# drives.net
KiCad netlist of a schematic drawn in EAGLE
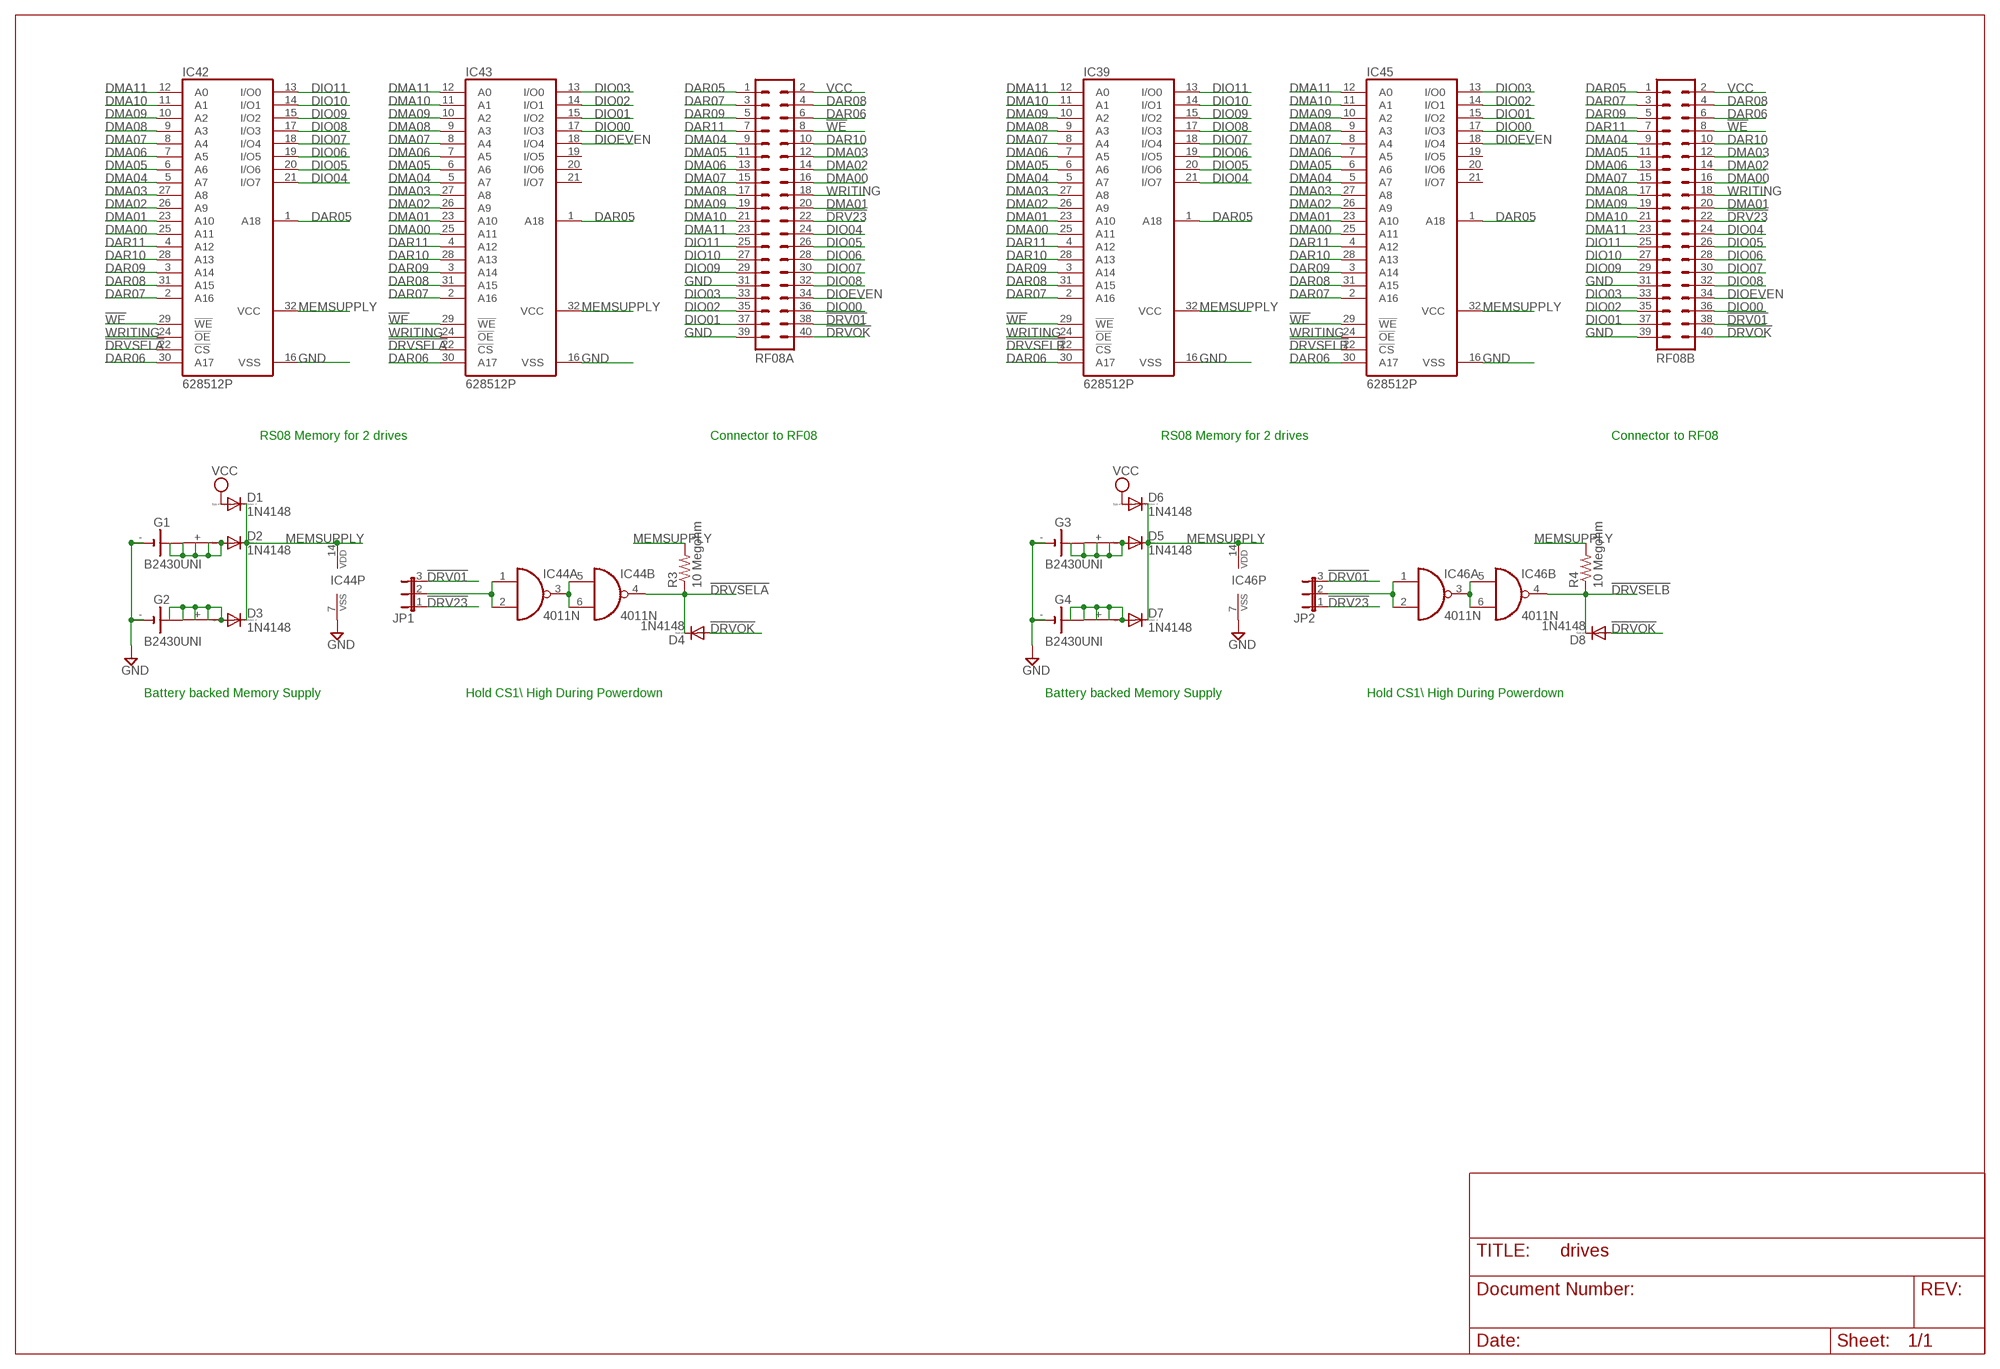
[diagram p0: schematic, sheet 1]

(export (version "E")
  (design (tool "Eeschema 10.0.6"))
  (components
    (comp (ref "D1")
      (value "1N4148")
      (footprint "eagle-import:DO35-10")
      (libsource (lib "eagle-import") (part "1N4148DO35-10"))
    )
    (comp (ref "D2")
      (value "1N4148")
      (footprint "eagle-import:DO35-10")
      (libsource (lib "eagle-import") (part "1N4148DO35-10"))
    )
    (comp (ref "D3")
      (value "1N4148")
      (footprint "eagle-import:DO35-10")
      (libsource (lib "eagle-import") (part "1N4148DO35-10"))
    )
    (comp (ref "D4")
      (value "1N4148")
      (footprint "eagle-import:DO35-10")
      (libsource (lib "eagle-import") (part "1N4148DO35-10"))
    )
    (comp (ref "D5")
      (value "1N4148")
      (footprint "eagle-import:DO35-10")
      (libsource (lib "eagle-import") (part "1N4148DO35-10"))
    )
    (comp (ref "D6")
      (value "1N4148")
      (footprint "eagle-import:DO35-10")
      (libsource (lib "eagle-import") (part "1N4148DO35-10"))
    )
    (comp (ref "D7")
      (value "1N4148")
      (footprint "eagle-import:DO35-10")
      (libsource (lib "eagle-import") (part "1N4148DO35-10"))
    )
    (comp (ref "D8")
      (value "1N4148")
      (footprint "eagle-import:DO35-10")
      (libsource (lib "eagle-import") (part "1N4148DO35-10"))
    )
    (comp (ref "G1")
      (value "B2430UNI")
      (footprint "eagle-import:B2430UNI")
      (libsource (lib "eagle-import") (part "B2430UNI"))
    )
    (comp (ref "G2")
      (value "B2430UNI")
      (footprint "eagle-import:B2430UNI")
      (libsource (lib "eagle-import") (part "B2430UNI"))
    )
    (comp (ref "G3")
      (value "B2430UNI")
      (footprint "eagle-import:B2430UNI")
      (libsource (lib "eagle-import") (part "B2430UNI"))
    )
    (comp (ref "G4")
      (value "B2430UNI")
      (footprint "eagle-import:B2430UNI")
      (libsource (lib "eagle-import") (part "B2430UNI"))
    )
    (comp (ref "IC39")
      (value "628512P")
      (footprint "eagle-import:DIL32")
      (libsource (lib "eagle-import") (part "628512P"))
    )
    (comp (ref "IC42")
      (value "628512P")
      (footprint "eagle-import:DIL32")
      (libsource (lib "eagle-import") (part "628512P"))
    )
    (comp (ref "IC43")
      (value "628512P")
      (footprint "eagle-import:DIL32")
      (libsource (lib "eagle-import") (part "628512P"))
    )
    (comp (ref "IC44")
      (value "4011N")
      (footprint "eagle-import:DIL14")
      (libsource (lib "eagle-import") (part "4011N"))
    )
    (comp (ref "IC45")
      (value "628512P")
      (footprint "eagle-import:DIL32")
      (libsource (lib "eagle-import") (part "628512P"))
    )
    (comp (ref "IC46")
      (value "4011N")
      (footprint "eagle-import:DIL14")
      (libsource (lib "eagle-import") (part "4011N"))
    )
    (comp (ref "JP1")
      (value "JP2E")
      (footprint "eagle-import:JP2")
      (libsource (lib "eagle-import") (part "JP2E"))
    )
    (comp (ref "JP2")
      (value "JP2E")
      (footprint "eagle-import:JP2")
      (libsource (lib "eagle-import") (part "JP2E"))
    )
    (comp (ref "R3")
      (value "10 Megohm")
      (footprint "eagle-import:0207_10")
      (libsource (lib "eagle-import") (part "R-US_0207/10"))
    )
    (comp (ref "R4")
      (value "10 Megohm")
      (footprint "eagle-import:0207_10")
      (libsource (lib "eagle-import") (part "R-US_0207/10"))
    )
    (comp (ref "RF08A")
      (value "MA20-2")
      (footprint "eagle-import:MA20-2")
      (libsource (lib "eagle-import") (part "MA20-2"))
    )
    (comp (ref "RF08B")
      (value "MA20-2")
      (footprint "eagle-import:MA20-2")
      (libsource (lib "eagle-import") (part "MA20-2"))
    )
  )
  (nets
    (net (code "1") (name "/DAR05") (class "Default")
      (node (ref "IC39") (pin "1") (pinfunction "A18_1") (pintype "input"))
      (node (ref "IC42") (pin "1") (pinfunction "A18_1") (pintype "input"))
      (node (ref "IC43") (pin "1") (pinfunction "A18_1") (pintype "input"))
      (node (ref "IC45") (pin "1") (pinfunction "A18_1") (pintype "input"))
      (node (ref "RF08A") (pin "1") (pinfunction "1_1") (pintype "passive"))
      (node (ref "RF08B") (pin "1") (pinfunction "1_1") (pintype "passive"))
    )
    (net (code "2") (name "/DAR06") (class "Default")
      (node (ref "IC39") (pin "30") (pinfunction "A17_30") (pintype "input"))
      (node (ref "IC42") (pin "30") (pinfunction "A17_30") (pintype "input"))
      (node (ref "IC43") (pin "30") (pinfunction "A17_30") (pintype "input"))
      (node (ref "IC45") (pin "30") (pinfunction "A17_30") (pintype "input"))
      (node (ref "RF08A") (pin "6") (pinfunction "6_6") (pintype "passive"))
      (node (ref "RF08B") (pin "6") (pinfunction "6_6") (pintype "passive"))
    )
    (net (code "3") (name "/DAR07") (class "Default")
      (node (ref "IC39") (pin "2") (pinfunction "A16_2") (pintype "input"))
      (node (ref "IC42") (pin "2") (pinfunction "A16_2") (pintype "input"))
      (node (ref "IC43") (pin "2") (pinfunction "A16_2") (pintype "input"))
      (node (ref "IC45") (pin "2") (pinfunction "A16_2") (pintype "input"))
      (node (ref "RF08A") (pin "3") (pinfunction "3_3") (pintype "passive"))
      (node (ref "RF08B") (pin "3") (pinfunction "3_3") (pintype "passive"))
    )
    (net (code "4") (name "/DAR08") (class "Default")
      (node (ref "IC39") (pin "31") (pinfunction "A15_31") (pintype "input"))
      (node (ref "IC42") (pin "31") (pinfunction "A15_31") (pintype "input"))
      (node (ref "IC43") (pin "31") (pinfunction "A15_31") (pintype "input"))
      (node (ref "IC45") (pin "31") (pinfunction "A15_31") (pintype "input"))
      (node (ref "RF08A") (pin "4") (pinfunction "4_4") (pintype "passive"))
      (node (ref "RF08B") (pin "4") (pinfunction "4_4") (pintype "passive"))
    )
    (net (code "5") (name "/DAR09") (class "Default")
      (node (ref "IC39") (pin "3") (pinfunction "A14_3") (pintype "input"))
      (node (ref "IC42") (pin "3") (pinfunction "A14_3") (pintype "input"))
      (node (ref "IC43") (pin "3") (pinfunction "A14_3") (pintype "input"))
      (node (ref "IC45") (pin "3") (pinfunction "A14_3") (pintype "input"))
      (node (ref "RF08A") (pin "5") (pinfunction "5_5") (pintype "passive"))
      (node (ref "RF08B") (pin "5") (pinfunction "5_5") (pintype "passive"))
    )
    (net (code "6") (name "/DAR10") (class "Default")
      (node (ref "IC39") (pin "28") (pinfunction "A13_28") (pintype "input"))
      (node (ref "IC42") (pin "28") (pinfunction "A13_28") (pintype "input"))
      (node (ref "IC43") (pin "28") (pinfunction "A13_28") (pintype "input"))
      (node (ref "IC45") (pin "28") (pinfunction "A13_28") (pintype "input"))
      (node (ref "RF08A") (pin "10") (pinfunction "10_10") (pintype "passive"))
      (node (ref "RF08B") (pin "10") (pinfunction "10_10") (pintype "passive"))
    )
    (net (code "7") (name "/DAR11") (class "Default")
      (node (ref "IC39") (pin "4") (pinfunction "A12_4") (pintype "input"))
      (node (ref "IC42") (pin "4") (pinfunction "A12_4") (pintype "input"))
      (node (ref "IC43") (pin "4") (pinfunction "A12_4") (pintype "input"))
      (node (ref "IC45") (pin "4") (pinfunction "A12_4") (pintype "input"))
      (node (ref "RF08A") (pin "7") (pinfunction "7_7") (pintype "passive"))
      (node (ref "RF08B") (pin "7") (pinfunction "7_7") (pintype "passive"))
    )
    (net (code "8") (name "/DIO00") (class "Default")
      (node (ref "IC43") (pin "17") (pinfunction "I/O3_17") (pintype "bidirectional"))
      (node (ref "IC45") (pin "17") (pinfunction "I/O3_17") (pintype "bidirectional"))
      (node (ref "RF08A") (pin "36") (pinfunction "36_36") (pintype "passive"))
      (node (ref "RF08B") (pin "36") (pinfunction "36_36") (pintype "passive"))
    )
    (net (code "9") (name "/DIO01") (class "Default")
      (node (ref "IC43") (pin "15") (pinfunction "I/O2_15") (pintype "bidirectional"))
      (node (ref "IC45") (pin "15") (pinfunction "I/O2_15") (pintype "bidirectional"))
      (node (ref "RF08A") (pin "37") (pinfunction "37_37") (pintype "passive"))
      (node (ref "RF08B") (pin "37") (pinfunction "37_37") (pintype "passive"))
    )
    (net (code "10") (name "/DIO02") (class "Default")
      (node (ref "IC43") (pin "14") (pinfunction "I/O1_14") (pintype "bidirectional"))
      (node (ref "IC45") (pin "14") (pinfunction "I/O1_14") (pintype "bidirectional"))
      (node (ref "RF08A") (pin "35") (pinfunction "35_35") (pintype "passive"))
      (node (ref "RF08B") (pin "35") (pinfunction "35_35") (pintype "passive"))
    )
    (net (code "11") (name "/DIO03") (class "Default")
      (node (ref "IC43") (pin "13") (pinfunction "I/O0_13") (pintype "bidirectional"))
      (node (ref "IC45") (pin "13") (pinfunction "I/O0_13") (pintype "bidirectional"))
      (node (ref "RF08A") (pin "33") (pinfunction "33_33") (pintype "passive"))
      (node (ref "RF08B") (pin "33") (pinfunction "33_33") (pintype "passive"))
    )
    (net (code "12") (name "/DIO04") (class "Default")
      (node (ref "IC39") (pin "21") (pinfunction "I/O7_21") (pintype "bidirectional"))
      (node (ref "IC42") (pin "21") (pinfunction "I/O7_21") (pintype "bidirectional"))
      (node (ref "RF08A") (pin "24") (pinfunction "24_24") (pintype "passive"))
      (node (ref "RF08B") (pin "24") (pinfunction "24_24") (pintype "passive"))
    )
    (net (code "13") (name "/DIO05") (class "Default")
      (node (ref "IC39") (pin "20") (pinfunction "I/O6_20") (pintype "bidirectional"))
      (node (ref "IC42") (pin "20") (pinfunction "I/O6_20") (pintype "bidirectional"))
      (node (ref "RF08A") (pin "26") (pinfunction "26_26") (pintype "passive"))
      (node (ref "RF08B") (pin "26") (pinfunction "26_26") (pintype "passive"))
    )
    (net (code "14") (name "/DIO06") (class "Default")
      (node (ref "IC39") (pin "19") (pinfunction "I/O5_19") (pintype "bidirectional"))
      (node (ref "IC42") (pin "19") (pinfunction "I/O5_19") (pintype "bidirectional"))
      (node (ref "RF08A") (pin "28") (pinfunction "28_28") (pintype "passive"))
      (node (ref "RF08B") (pin "28") (pinfunction "28_28") (pintype "passive"))
    )
    (net (code "15") (name "/DIO07") (class "Default")
      (node (ref "IC39") (pin "18") (pinfunction "I/O4_18") (pintype "bidirectional"))
      (node (ref "IC42") (pin "18") (pinfunction "I/O4_18") (pintype "bidirectional"))
      (node (ref "RF08A") (pin "30") (pinfunction "30_30") (pintype "passive"))
      (node (ref "RF08B") (pin "30") (pinfunction "30_30") (pintype "passive"))
    )
    (net (code "16") (name "/DIO08") (class "Default")
      (node (ref "IC39") (pin "17") (pinfunction "I/O3_17") (pintype "bidirectional"))
      (node (ref "IC42") (pin "17") (pinfunction "I/O3_17") (pintype "bidirectional"))
      (node (ref "RF08A") (pin "32") (pinfunction "32_32") (pintype "passive"))
      (node (ref "RF08B") (pin "32") (pinfunction "32_32") (pintype "passive"))
    )
    (net (code "17") (name "/DIO09") (class "Default")
      (node (ref "IC39") (pin "15") (pinfunction "I/O2_15") (pintype "bidirectional"))
      (node (ref "IC42") (pin "15") (pinfunction "I/O2_15") (pintype "bidirectional"))
      (node (ref "RF08A") (pin "29") (pinfunction "29_29") (pintype "passive"))
      (node (ref "RF08B") (pin "29") (pinfunction "29_29") (pintype "passive"))
    )
    (net (code "18") (name "/DIO10") (class "Default")
      (node (ref "IC39") (pin "14") (pinfunction "I/O1_14") (pintype "bidirectional"))
      (node (ref "IC42") (pin "14") (pinfunction "I/O1_14") (pintype "bidirectional"))
      (node (ref "RF08A") (pin "27") (pinfunction "27_27") (pintype "passive"))
      (node (ref "RF08B") (pin "27") (pinfunction "27_27") (pintype "passive"))
    )
    (net (code "19") (name "/DIO11") (class "Default")
      (node (ref "IC39") (pin "13") (pinfunction "I/O0_13") (pintype "bidirectional"))
      (node (ref "IC42") (pin "13") (pinfunction "I/O0_13") (pintype "bidirectional"))
      (node (ref "RF08A") (pin "25") (pinfunction "25_25") (pintype "passive"))
      (node (ref "RF08B") (pin "25") (pinfunction "25_25") (pintype "passive"))
    )
    (net (code "20") (name "/DIOEVEN") (class "Default")
      (node (ref "IC43") (pin "18") (pinfunction "I/O4_18") (pintype "bidirectional"))
      (node (ref "IC45") (pin "18") (pinfunction "I/O4_18") (pintype "bidirectional"))
      (node (ref "RF08A") (pin "34") (pinfunction "34_34") (pintype "passive"))
      (node (ref "RF08B") (pin "34") (pinfunction "34_34") (pintype "passive"))
    )
    (net (code "21") (name "/DMA00") (class "Default")
      (node (ref "IC39") (pin "25") (pinfunction "A11_25") (pintype "input"))
      (node (ref "IC42") (pin "25") (pinfunction "A11_25") (pintype "input"))
      (node (ref "IC43") (pin "25") (pinfunction "A11_25") (pintype "input"))
      (node (ref "IC45") (pin "25") (pinfunction "A11_25") (pintype "input"))
      (node (ref "RF08A") (pin "16") (pinfunction "16_16") (pintype "passive"))
      (node (ref "RF08B") (pin "16") (pinfunction "16_16") (pintype "passive"))
    )
    (net (code "22") (name "/DMA01") (class "Default")
      (node (ref "IC39") (pin "23") (pinfunction "A10_23") (pintype "input"))
      (node (ref "IC42") (pin "23") (pinfunction "A10_23") (pintype "input"))
      (node (ref "IC43") (pin "23") (pinfunction "A10_23") (pintype "input"))
      (node (ref "IC45") (pin "23") (pinfunction "A10_23") (pintype "input"))
      (node (ref "RF08A") (pin "20") (pinfunction "20_20") (pintype "passive"))
      (node (ref "RF08B") (pin "20") (pinfunction "20_20") (pintype "passive"))
    )
    (net (code "23") (name "/DMA02") (class "Default")
      (node (ref "IC39") (pin "26") (pinfunction "A9_26") (pintype "input"))
      (node (ref "IC42") (pin "26") (pinfunction "A9_26") (pintype "input"))
      (node (ref "IC43") (pin "26") (pinfunction "A9_26") (pintype "input"))
      (node (ref "IC45") (pin "26") (pinfunction "A9_26") (pintype "input"))
      (node (ref "RF08A") (pin "14") (pinfunction "14_14") (pintype "passive"))
      (node (ref "RF08B") (pin "14") (pinfunction "14_14") (pintype "passive"))
    )
    (net (code "24") (name "/DMA03") (class "Default")
      (node (ref "IC39") (pin "27") (pinfunction "A8_27") (pintype "input"))
      (node (ref "IC42") (pin "27") (pinfunction "A8_27") (pintype "input"))
      (node (ref "IC43") (pin "27") (pinfunction "A8_27") (pintype "input"))
      (node (ref "IC45") (pin "27") (pinfunction "A8_27") (pintype "input"))
      (node (ref "RF08A") (pin "12") (pinfunction "12_12") (pintype "passive"))
      (node (ref "RF08B") (pin "12") (pinfunction "12_12") (pintype "passive"))
    )
    (net (code "25") (name "/DMA04") (class "Default")
      (node (ref "IC39") (pin "5") (pinfunction "A7_5") (pintype "input"))
      (node (ref "IC42") (pin "5") (pinfunction "A7_5") (pintype "input"))
      (node (ref "IC43") (pin "5") (pinfunction "A7_5") (pintype "input"))
      (node (ref "IC45") (pin "5") (pinfunction "A7_5") (pintype "input"))
      (node (ref "RF08A") (pin "9") (pinfunction "9_9") (pintype "passive"))
      (node (ref "RF08B") (pin "9") (pinfunction "9_9") (pintype "passive"))
    )
    (net (code "26") (name "/DMA05") (class "Default")
      (node (ref "IC39") (pin "6") (pinfunction "A6_6") (pintype "input"))
      (node (ref "IC42") (pin "6") (pinfunction "A6_6") (pintype "input"))
      (node (ref "IC43") (pin "6") (pinfunction "A6_6") (pintype "input"))
      (node (ref "IC45") (pin "6") (pinfunction "A6_6") (pintype "input"))
      (node (ref "RF08A") (pin "11") (pinfunction "11_11") (pintype "passive"))
      (node (ref "RF08B") (pin "11") (pinfunction "11_11") (pintype "passive"))
    )
    (net (code "27") (name "/DMA06") (class "Default")
      (node (ref "IC39") (pin "7") (pinfunction "A5_7") (pintype "input"))
      (node (ref "IC42") (pin "7") (pinfunction "A5_7") (pintype "input"))
      (node (ref "IC43") (pin "7") (pinfunction "A5_7") (pintype "input"))
      (node (ref "IC45") (pin "7") (pinfunction "A5_7") (pintype "input"))
      (node (ref "RF08A") (pin "13") (pinfunction "13_13") (pintype "passive"))
      (node (ref "RF08B") (pin "13") (pinfunction "13_13") (pintype "passive"))
    )
    (net (code "28") (name "/DMA07") (class "Default")
      (node (ref "IC39") (pin "8") (pinfunction "A4_8") (pintype "input"))
      (node (ref "IC42") (pin "8") (pinfunction "A4_8") (pintype "input"))
      (node (ref "IC43") (pin "8") (pinfunction "A4_8") (pintype "input"))
      (node (ref "IC45") (pin "8") (pinfunction "A4_8") (pintype "input"))
      (node (ref "RF08A") (pin "15") (pinfunction "15_15") (pintype "passive"))
      (node (ref "RF08B") (pin "15") (pinfunction "15_15") (pintype "passive"))
    )
    (net (code "29") (name "/DMA08") (class "Default")
      (node (ref "IC39") (pin "9") (pinfunction "A3_9") (pintype "input"))
      (node (ref "IC42") (pin "9") (pinfunction "A3_9") (pintype "input"))
      (node (ref "IC43") (pin "9") (pinfunction "A3_9") (pintype "input"))
      (node (ref "IC45") (pin "9") (pinfunction "A3_9") (pintype "input"))
      (node (ref "RF08A") (pin "17") (pinfunction "17_17") (pintype "passive"))
      (node (ref "RF08B") (pin "17") (pinfunction "17_17") (pintype "passive"))
    )
    (net (code "30") (name "/DMA09") (class "Default")
      (node (ref "IC39") (pin "10") (pinfunction "A2_10") (pintype "input"))
      (node (ref "IC42") (pin "10") (pinfunction "A2_10") (pintype "input"))
      (node (ref "IC43") (pin "10") (pinfunction "A2_10") (pintype "input"))
      (node (ref "IC45") (pin "10") (pinfunction "A2_10") (pintype "input"))
      (node (ref "RF08A") (pin "19") (pinfunction "19_19") (pintype "passive"))
      (node (ref "RF08B") (pin "19") (pinfunction "19_19") (pintype "passive"))
    )
    (net (code "31") (name "/DMA10") (class "Default")
      (node (ref "IC39") (pin "11") (pinfunction "A1_11") (pintype "input"))
      (node (ref "IC42") (pin "11") (pinfunction "A1_11") (pintype "input"))
      (node (ref "IC43") (pin "11") (pinfunction "A1_11") (pintype "input"))
      (node (ref "IC45") (pin "11") (pinfunction "A1_11") (pintype "input"))
      (node (ref "RF08A") (pin "21") (pinfunction "21_21") (pintype "passive"))
      (node (ref "RF08B") (pin "21") (pinfunction "21_21") (pintype "passive"))
    )
    (net (code "32") (name "/DMA11") (class "Default")
      (node (ref "IC39") (pin "12") (pinfunction "A0_12") (pintype "input"))
      (node (ref "IC42") (pin "12") (pinfunction "A0_12") (pintype "input"))
      (node (ref "IC43") (pin "12") (pinfunction "A0_12") (pintype "input"))
      (node (ref "IC45") (pin "12") (pinfunction "A0_12") (pintype "input"))
      (node (ref "RF08A") (pin "23") (pinfunction "23_23") (pintype "passive"))
      (node (ref "RF08B") (pin "23") (pinfunction "23_23") (pintype "passive"))
    )
    (net (code "33") (name "/MEMSUPPLY") (class "Default")
      (node (ref "D1") (pin "C") (pinfunction "C_C") (pintype "passive"))
      (node (ref "D2") (pin "C") (pinfunction "C_C") (pintype "passive"))
      (node (ref "D3") (pin "C") (pinfunction "C_C") (pintype "passive"))
      (node (ref "D5") (pin "C") (pinfunction "C_C") (pintype "passive"))
      (node (ref "D6") (pin "C") (pinfunction "C_C") (pintype "passive"))
      (node (ref "D7") (pin "C") (pinfunction "C_C") (pintype "passive"))
      (node (ref "IC39") (pin "32") (pinfunction "VCC_32") (pintype "power_in"))
      (node (ref "IC42") (pin "32") (pinfunction "VCC_32") (pintype "power_in"))
      (node (ref "IC43") (pin "32") (pinfunction "VCC_32") (pintype "power_in"))
      (node (ref "IC44") (pin "14") (pinfunction "VDD_14") (pintype "power_in"))
      (node (ref "IC45") (pin "32") (pinfunction "VCC_32") (pintype "power_in"))
      (node (ref "IC46") (pin "14") (pinfunction "VDD_14") (pintype "power_in"))
      (node (ref "R3") (pin "2") (pinfunction "2_2") (pintype "passive"))
      (node (ref "R4") (pin "2") (pinfunction "2_2") (pintype "passive"))
    )
    (net (code "34") (name "/WRITING") (class "Default")
      (node (ref "IC39") (pin "24") (pinfunction "~{OE}_24") (pintype "input"))
      (node (ref "IC42") (pin "24") (pinfunction "~{OE}_24") (pintype "input"))
      (node (ref "IC43") (pin "24") (pinfunction "~{OE}_24") (pintype "input"))
      (node (ref "IC45") (pin "24") (pinfunction "~{OE}_24") (pintype "input"))
      (node (ref "RF08A") (pin "18") (pinfunction "18_18") (pintype "passive"))
      (node (ref "RF08B") (pin "18") (pinfunction "18_18") (pintype "passive"))
    )
    (net (code "35") (name "/~{DRV01}") (class "Default")
      (node (ref "JP1") (pin "3") (pinfunction "3_3") (pintype "passive"))
      (node (ref "JP2") (pin "3") (pinfunction "3_3") (pintype "passive"))
      (node (ref "RF08A") (pin "38") (pinfunction "38_38") (pintype "passive"))
      (node (ref "RF08B") (pin "38") (pinfunction "38_38") (pintype "passive"))
    )
    (net (code "36") (name "/~{DRV23}") (class "Default")
      (node (ref "JP1") (pin "1") (pinfunction "1_1") (pintype "passive"))
      (node (ref "JP2") (pin "1") (pinfunction "1_1") (pintype "passive"))
      (node (ref "RF08A") (pin "22") (pinfunction "22_22") (pintype "passive"))
      (node (ref "RF08B") (pin "22") (pinfunction "22_22") (pintype "passive"))
    )
    (net (code "37") (name "/~{DRVOK}") (class "Default")
      (node (ref "D4") (pin "A") (pinfunction "A_A") (pintype "passive"))
      (node (ref "D8") (pin "A") (pinfunction "A_A") (pintype "passive"))
      (node (ref "RF08A") (pin "40") (pinfunction "40_40") (pintype "passive"))
      (node (ref "RF08B") (pin "40") (pinfunction "40_40") (pintype "passive"))
    )
    (net (code "38") (name "/~{DRVSELA}") (class "Default")
      (node (ref "D4") (pin "C") (pinfunction "C_C") (pintype "passive"))
      (node (ref "IC42") (pin "22") (pinfunction "~{CS}_22") (pintype "input"))
      (node (ref "IC43") (pin "22") (pinfunction "~{CS}_22") (pintype "input"))
      (node (ref "IC44") (pin "4") (pinfunction "O_4") (pintype "output"))
      (node (ref "R3") (pin "1") (pinfunction "1_1") (pintype "passive"))
    )
    (net (code "39") (name "/~{DRVSELB}") (class "Default")
      (node (ref "D8") (pin "C") (pinfunction "C_C") (pintype "passive"))
      (node (ref "IC39") (pin "22") (pinfunction "~{CS}_22") (pintype "input"))
      (node (ref "IC45") (pin "22") (pinfunction "~{CS}_22") (pintype "input"))
      (node (ref "IC46") (pin "4") (pinfunction "O_4") (pintype "output"))
      (node (ref "R4") (pin "1") (pinfunction "1_1") (pintype "passive"))
    )
    (net (code "40") (name "/~{WE}") (class "Default")
      (node (ref "IC39") (pin "29") (pinfunction "~{WE}_29") (pintype "input"))
      (node (ref "IC42") (pin "29") (pinfunction "~{WE}_29") (pintype "input"))
      (node (ref "IC43") (pin "29") (pinfunction "~{WE}_29") (pintype "input"))
      (node (ref "IC45") (pin "29") (pinfunction "~{WE}_29") (pintype "input"))
      (node (ref "RF08A") (pin "8") (pinfunction "8_8") (pintype "passive"))
      (node (ref "RF08B") (pin "8") (pinfunction "8_8") (pintype "passive"))
    )
    (net (code "41") (name "GND") (class "Default")
      (node (ref "G1") (pin "-") (pinfunction "-_-") (pintype "passive"))
      (node (ref "G1") (pin "-@1") (pinfunction "-_-@1") (pintype "passive"))
      (node (ref "G2") (pin "-") (pinfunction "-_-") (pintype "passive"))
      (node (ref "G2") (pin "-@1") (pinfunction "-_-@1") (pintype "passive"))
      (node (ref "G3") (pin "-") (pinfunction "-_-") (pintype "passive"))
      (node (ref "G3") (pin "-@1") (pinfunction "-_-@1") (pintype "passive"))
      (node (ref "G4") (pin "-") (pinfunction "-_-") (pintype "passive"))
      (node (ref "G4") (pin "-@1") (pinfunction "-_-@1") (pintype "passive"))
      (node (ref "IC39") (pin "16") (pinfunction "VSS_16") (pintype "power_in"))
      (node (ref "IC42") (pin "16") (pinfunction "VSS_16") (pintype "power_in"))
      (node (ref "IC43") (pin "16") (pinfunction "VSS_16") (pintype "power_in"))
      (node (ref "IC44") (pin "7") (pinfunction "VSS_7") (pintype "power_in"))
      (node (ref "IC45") (pin "16") (pinfunction "VSS_16") (pintype "power_in"))
      (node (ref "IC46") (pin "7") (pinfunction "VSS_7") (pintype "power_in"))
      (node (ref "RF08A") (pin "31") (pinfunction "31_31") (pintype "passive"))
      (node (ref "RF08A") (pin "39") (pinfunction "39_39") (pintype "passive"))
      (node (ref "RF08B") (pin "31") (pinfunction "31_31") (pintype "passive"))
      (node (ref "RF08B") (pin "39") (pinfunction "39_39") (pintype "passive"))
    )
    (net (code "42") (name "Net-(D2-PadA)") (class "Default")
      (node (ref "D2") (pin "A") (pinfunction "A_A") (pintype "passive"))
      (node (ref "G1") (pin "+") (pinfunction "+_+") (pintype "passive"))
      (node (ref "G1") (pin "+@1") (pinfunction "+_+@1") (pintype "passive"))
      (node (ref "G1") (pin "+@2") (pinfunction "+_+@2") (pintype "passive"))
      (node (ref "G1") (pin "+@3") (pinfunction "+_+@3") (pintype "passive"))
      (node (ref "G1") (pin "+@4") (pinfunction "+_+@4") (pintype "passive"))
    )
    (net (code "43") (name "Net-(D3-PadA)") (class "Default")
      (node (ref "D3") (pin "A") (pinfunction "A_A") (pintype "passive"))
      (node (ref "G2") (pin "+") (pinfunction "+_+") (pintype "passive"))
      (node (ref "G2") (pin "+@1") (pinfunction "+_+@1") (pintype "passive"))
      (node (ref "G2") (pin "+@2") (pinfunction "+_+@2") (pintype "passive"))
      (node (ref "G2") (pin "+@3") (pinfunction "+_+@3") (pintype "passive"))
      (node (ref "G2") (pin "+@4") (pinfunction "+_+@4") (pintype "passive"))
    )
    (net (code "44") (name "Net-(D5-PadA)") (class "Default")
      (node (ref "D5") (pin "A") (pinfunction "A_A") (pintype "passive"))
      (node (ref "G3") (pin "+") (pinfunction "+_+") (pintype "passive"))
      (node (ref "G3") (pin "+@1") (pinfunction "+_+@1") (pintype "passive"))
      (node (ref "G3") (pin "+@2") (pinfunction "+_+@2") (pintype "passive"))
      (node (ref "G3") (pin "+@3") (pinfunction "+_+@3") (pintype "passive"))
      (node (ref "G3") (pin "+@4") (pinfunction "+_+@4") (pintype "passive"))
    )
    (net (code "45") (name "Net-(D7-PadA)") (class "Default")
      (node (ref "D7") (pin "A") (pinfunction "A_A") (pintype "passive"))
      (node (ref "G4") (pin "+") (pinfunction "+_+") (pintype "passive"))
      (node (ref "G4") (pin "+@1") (pinfunction "+_+@1") (pintype "passive"))
      (node (ref "G4") (pin "+@2") (pinfunction "+_+@2") (pintype "passive"))
      (node (ref "G4") (pin "+@3") (pinfunction "+_+@3") (pintype "passive"))
      (node (ref "G4") (pin "+@4") (pinfunction "+_+@4") (pintype "passive"))
    )
    (net (code "46") (name "Net-(IC44A-I0)") (class "Default")
      (node (ref "IC44") (pin "1") (pinfunction "I0_1") (pintype "input"))
      (node (ref "IC44") (pin "2") (pinfunction "I1_2") (pintype "input"))
      (node (ref "JP1") (pin "2") (pinfunction "2_2") (pintype "passive"))
    )
    (net (code "47") (name "Net-(IC44A-O)") (class "Default")
      (node (ref "IC44") (pin "3") (pinfunction "O_3") (pintype "output"))
      (node (ref "IC44") (pin "5") (pinfunction "I0_5") (pintype "input"))
      (node (ref "IC44") (pin "6") (pinfunction "I1_6") (pintype "input"))
    )
    (net (code "48") (name "Net-(IC46A-I0)") (class "Default")
      (node (ref "IC46") (pin "1") (pinfunction "I0_1") (pintype "input"))
      (node (ref "IC46") (pin "2") (pinfunction "I1_2") (pintype "input"))
      (node (ref "JP2") (pin "2") (pinfunction "2_2") (pintype "passive"))
    )
    (net (code "49") (name "Net-(IC46A-O)") (class "Default")
      (node (ref "IC46") (pin "3") (pinfunction "O_3") (pintype "output"))
      (node (ref "IC46") (pin "5") (pinfunction "I0_5") (pintype "input"))
      (node (ref "IC46") (pin "6") (pinfunction "I1_6") (pintype "input"))
    )
    (net (code "50") (name "VCC") (class "Default")
      (node (ref "D1") (pin "A") (pinfunction "A_A") (pintype "passive"))
      (node (ref "D6") (pin "A") (pinfunction "A_A") (pintype "passive"))
      (node (ref "RF08A") (pin "2") (pinfunction "2_2") (pintype "passive"))
      (node (ref "RF08B") (pin "2") (pinfunction "2_2") (pintype "passive"))
    )
    (net (code "51") (name "unconnected-(IC43-I{slash}O5-Pad19)") (class "Default")
      (node (ref "IC43") (pin "19") (pinfunction "I/O5_19") (pintype "bidirectional"))
    )
    (net (code "52") (name "unconnected-(IC43-I{slash}O6-Pad20)") (class "Default")
      (node (ref "IC43") (pin "20") (pinfunction "I/O6_20") (pintype "bidirectional"))
    )
    (net (code "53") (name "unconnected-(IC43-I{slash}O7-Pad21)") (class "Default")
      (node (ref "IC43") (pin "21") (pinfunction "I/O7_21") (pintype "bidirectional"))
    )
    (net (code "54") (name "unconnected-(IC45-I{slash}O5-Pad19)") (class "Default")
      (node (ref "IC45") (pin "19") (pinfunction "I/O5_19") (pintype "bidirectional"))
    )
    (net (code "55") (name "unconnected-(IC45-I{slash}O6-Pad20)") (class "Default")
      (node (ref "IC45") (pin "20") (pinfunction "I/O6_20") (pintype "bidirectional"))
    )
    (net (code "56") (name "unconnected-(IC45-I{slash}O7-Pad21)") (class "Default")
      (node (ref "IC45") (pin "21") (pinfunction "I/O7_21") (pintype "bidirectional"))
    )
  )
)
